# ProgCalc.net
KiCad netlist of a schematic drawn in EAGLE
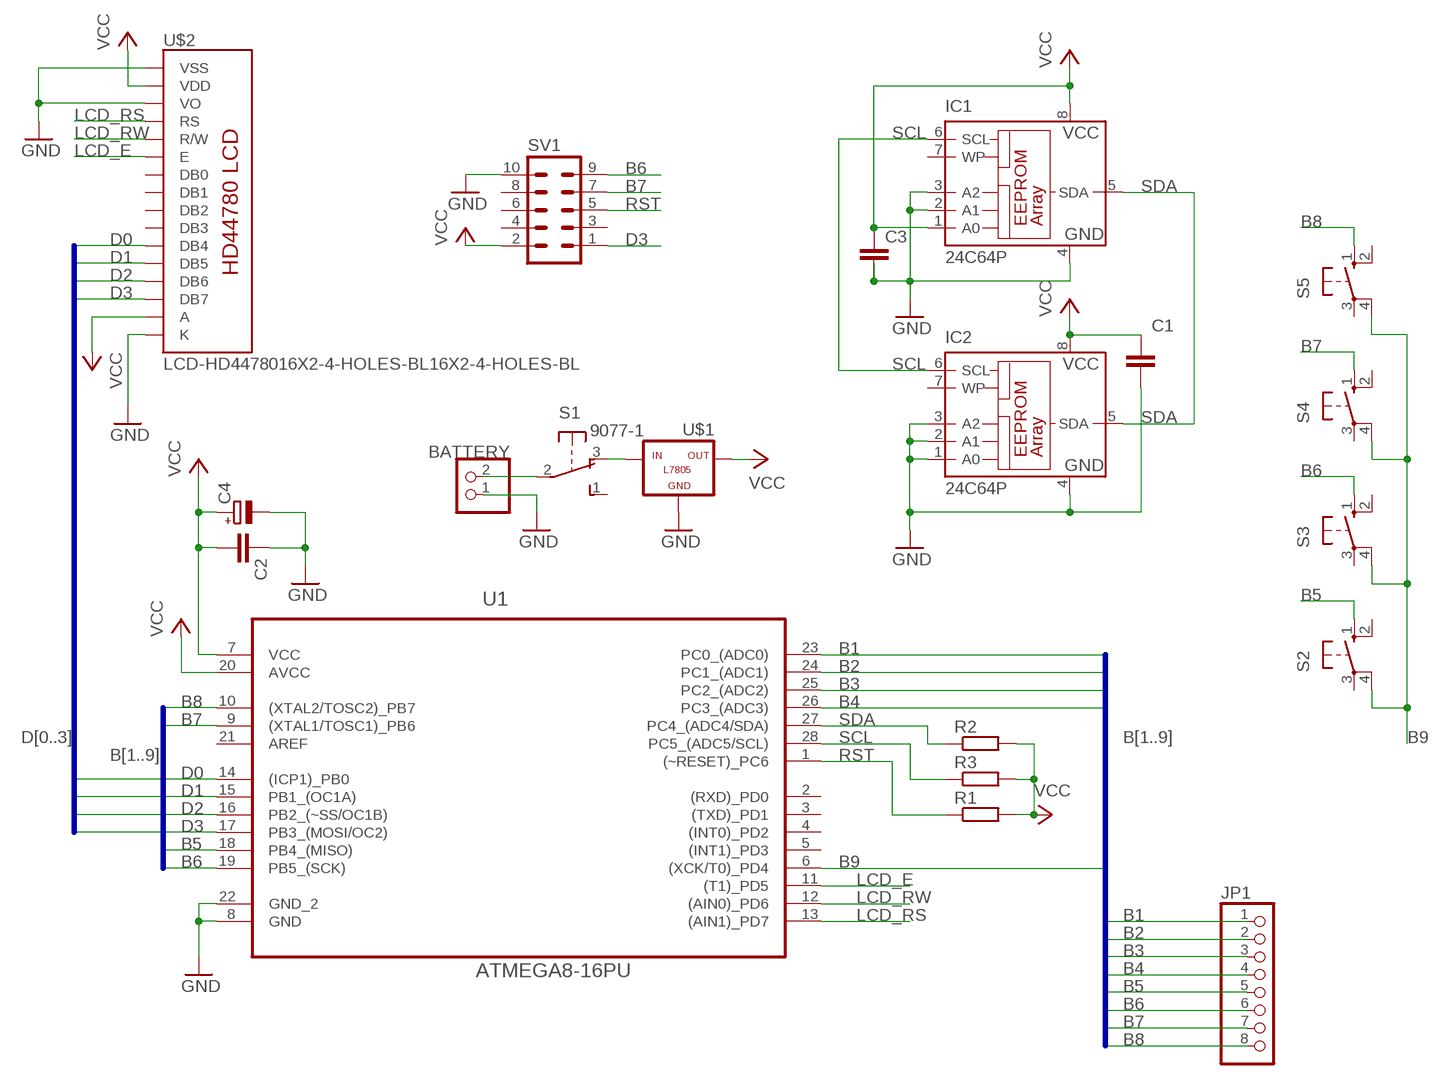
[diagram p0: schematic, sheet 1]

(export (version "E")
  (design (tool "Eeschema 10.0.6"))
  (components
    (comp (ref "BATTERY")
      (value "PINHD-1X2/90")
      (footprint "eagle-import:1X02_90")
      (libsource (lib "eagle-import") (part "PINHD-1X2/90"))
    )
    (comp (ref "C1")
      (value "C-EU025-025X050")
      (footprint "eagle-import:C025-025X050")
      (libsource (lib "eagle-import") (part "C-EU025-025X050"))
    )
    (comp (ref "C2")
      (value "C-EU025-025X050")
      (footprint "eagle-import:C025-025X050")
      (libsource (lib "eagle-import") (part "C-EU025-025X050"))
    )
    (comp (ref "C3")
      (value "C-EU025-025X050")
      (footprint "eagle-import:C025-025X050")
      (libsource (lib "eagle-import") (part "C-EU025-025X050"))
    )
    (comp (ref "C4")
      (value "CPOL-EUE1.8-4")
      (footprint "eagle-import:E1,8-4")
      (libsource (lib "eagle-import") (part "CPOL-EUE1.8-4"))
    )
    (comp (ref "IC1")
      (value "24C64P")
      (footprint "eagle-import:DIL8")
      (fields (field (name "MF") "RAMTRON INTERNATIONAL CORP") (field (name "MPN") "FM24C64-P"))
      (libsource (lib "eagle-import") (part "24PC64"))
    )
    (comp (ref "IC2")
      (value "24C64P")
      (footprint "eagle-import:DIL8")
      (fields (field (name "MF") "RAMTRON INTERNATIONAL CORP") (field (name "MPN") "FM24C64-P"))
      (libsource (lib "eagle-import") (part "24PC64"))
    )
    (comp (ref "JP1")
      (value "PINHD-1X8/90")
      (footprint "eagle-import:1X08_90")
      (libsource (lib "eagle-import") (part "PINHD-1X8/90"))
    )
    (comp (ref "R1")
      (value "R-EU_0204/7")
      (footprint "eagle-import:0204_7")
      (libsource (lib "eagle-import") (part "R-EU_0204/7"))
    )
    (comp (ref "R2")
      (value "R-EU_0204/7")
      (footprint "eagle-import:0204_7")
      (libsource (lib "eagle-import") (part "R-EU_0204/7"))
    )
    (comp (ref "R3")
      (value "R-EU_0204/7")
      (footprint "eagle-import:0204_7")
      (libsource (lib "eagle-import") (part "R-EU_0204/7"))
    )
    (comp (ref "S1")
      (value "9077-1")
      (footprint "eagle-import:9077-1")
      (libsource (lib "eagle-import") (part "9077-1"))
    )
    (comp (ref "S2")
      (value "10-XX")
      (footprint "eagle-import:B3F-10XX")
      (fields (field (name "MPN") "B3F-1000"))
      (libsource (lib "eagle-import") (part "10-XX"))
    )
    (comp (ref "S3")
      (value "10-XX")
      (footprint "eagle-import:B3F-10XX")
      (fields (field (name "MPN") "B3F-1000"))
      (libsource (lib "eagle-import") (part "10-XX"))
    )
    (comp (ref "S4")
      (value "10-XX")
      (footprint "eagle-import:B3F-10XX")
      (fields (field (name "MPN") "B3F-1000"))
      (libsource (lib "eagle-import") (part "10-XX"))
    )
    (comp (ref "S5")
      (value "10-XX")
      (footprint "eagle-import:B3F-10XX")
      (fields (field (name "MPN") "B3F-1000"))
      (libsource (lib "eagle-import") (part "10-XX"))
    )
    (comp (ref "SV1")
      (value "ML10L")
      (footprint "eagle-import:ML10L")
      (libsource (lib "eagle-import") (part "ML10L"))
    )
    (comp (ref "U$1")
      (value "-L7805")
      (footprint "eagle-import:L7805")
      (libsource (lib "eagle-import") (part "-L7805"))
    )
    (comp (ref "U$2")
      (value "LCD-HD4478016X2-4-HOLES-BL16X2-4-HOLES-BL")
      (footprint "eagle-import:LCD-16X2-4HOLES-BL")
      (libsource (lib "eagle-import") (part "LCD-HD4478016X2-4-HOLES-BL16X2-4-HOLES-BL"))
    )
    (comp (ref "U1")
      (value "ATMEGA8-16PU")
      (footprint "eagle-import:DIP254P762X457-28")
      (libsource (lib "eagle-import") (part "ATMEGA8-16PU"))
    )
  )
  (nets
    (net (code "1") (name "/B1") (class "Default")
      (node (ref "JP1") (pin "1") (pinfunction "1_1") (pintype "passive"))
      (node (ref "U1") (pin "23") (pinfunction "PC0_(ADC0)_23") (pintype "bidirectional"))
    )
    (net (code "2") (name "/B2") (class "Default")
      (node (ref "JP1") (pin "2") (pinfunction "2_2") (pintype "passive"))
      (node (ref "U1") (pin "24") (pinfunction "PC1_(ADC1)_24") (pintype "bidirectional"))
    )
    (net (code "3") (name "/B3") (class "Default")
      (node (ref "JP1") (pin "3") (pinfunction "3_3") (pintype "passive"))
      (node (ref "U1") (pin "25") (pinfunction "PC2_(ADC2)_25") (pintype "bidirectional"))
    )
    (net (code "4") (name "/B4") (class "Default")
      (node (ref "JP1") (pin "4") (pinfunction "4_4") (pintype "passive"))
      (node (ref "U1") (pin "26") (pinfunction "PC3_(ADC3)_26") (pintype "bidirectional"))
    )
    (net (code "5") (name "/B5") (class "Default")
      (node (ref "JP1") (pin "5") (pinfunction "5_5") (pintype "passive"))
      (node (ref "S2") (pin "1") (pinfunction "S_1") (pintype "passive"))
      (node (ref "U1") (pin "18") (pinfunction "PB4_(MISO)_18") (pintype "bidirectional"))
    )
    (net (code "6") (name "/B6") (class "Default")
      (node (ref "JP1") (pin "6") (pinfunction "6_6") (pintype "passive"))
      (node (ref "S3") (pin "1") (pinfunction "S_1") (pintype "passive"))
      (node (ref "SV1") (pin "9") (pinfunction "9_9") (pintype "passive"))
      (node (ref "U1") (pin "19") (pinfunction "PB5_(SCK)_19") (pintype "bidirectional"))
    )
    (net (code "7") (name "/B7") (class "Default")
      (node (ref "JP1") (pin "7") (pinfunction "7_7") (pintype "passive"))
      (node (ref "S4") (pin "1") (pinfunction "S_1") (pintype "passive"))
      (node (ref "SV1") (pin "7") (pinfunction "7_7") (pintype "passive"))
      (node (ref "U1") (pin "9") (pinfunction "(XTAL1/TOSC1)_PB6_9") (pintype "input"))
    )
    (net (code "8") (name "/B8") (class "Default")
      (node (ref "JP1") (pin "8") (pinfunction "8_8") (pintype "passive"))
      (node (ref "S5") (pin "1") (pinfunction "S_1") (pintype "passive"))
      (node (ref "U1") (pin "10") (pinfunction "(XTAL2/TOSC2)_PB7_10") (pintype "input"))
    )
    (net (code "9") (name "/B9") (class "Default")
      (node (ref "S2") (pin "4") (pinfunction "P1_4") (pintype "passive"))
      (node (ref "S3") (pin "4") (pinfunction "P1_4") (pintype "passive"))
      (node (ref "S4") (pin "4") (pinfunction "P1_4") (pintype "passive"))
      (node (ref "S5") (pin "4") (pinfunction "P1_4") (pintype "passive"))
      (node (ref "U1") (pin "6") (pinfunction "(XCK/T0)_PD4_6") (pintype "bidirectional"))
    )
    (net (code "11") (name "/D0") (class "Default")
      (node (ref "U$2") (pin "11") (pinfunction "DB4_11") (pintype "bidirectional"))
      (node (ref "U1") (pin "14") (pinfunction "(ICP1)_PB0_14") (pintype "bidirectional"))
    )
    (net (code "12") (name "/D1") (class "Default")
      (node (ref "U$2") (pin "12") (pinfunction "DB5_12") (pintype "bidirectional"))
      (node (ref "U1") (pin "15") (pinfunction "PB1_(OC1A)_15") (pintype "bidirectional"))
    )
    (net (code "13") (name "/D2") (class "Default")
      (node (ref "U$2") (pin "13") (pinfunction "DB6_13") (pintype "bidirectional"))
      (node (ref "U1") (pin "16") (pinfunction "PB2_(~{SS/OC1B})_16") (pintype "bidirectional"))
    )
    (net (code "14") (name "/D3") (class "Default")
      (node (ref "SV1") (pin "1") (pinfunction "1_1") (pintype "passive"))
      (node (ref "U$2") (pin "14") (pinfunction "DB7_14") (pintype "bidirectional"))
      (node (ref "U1") (pin "17") (pinfunction "PB3_(MOSI/OC2)_17") (pintype "bidirectional"))
    )
    (net (code "16") (name "/LCD_E") (class "Default")
      (node (ref "U$2") (pin "6") (pinfunction "E_6") (pintype "input"))
      (node (ref "U1") (pin "11") (pinfunction "(T1)_PD5_11") (pintype "bidirectional"))
    )
    (net (code "17") (name "/LCD_RS") (class "Default")
      (node (ref "U$2") (pin "4") (pinfunction "RS_4") (pintype "input"))
      (node (ref "U1") (pin "13") (pinfunction "(AIN1)_PD7_13") (pintype "bidirectional"))
    )
    (net (code "18") (name "/LCD_RW") (class "Default")
      (node (ref "U$2") (pin "5") (pinfunction "R/W_5") (pintype "input"))
      (node (ref "U1") (pin "12") (pinfunction "(AIN0)_PD6_12") (pintype "bidirectional"))
    )
    (net (code "19") (name "/RST") (class "Default")
      (node (ref "R1") (pin "1") (pinfunction "1_1") (pintype "passive"))
      (node (ref "SV1") (pin "5") (pinfunction "5_5") (pintype "passive"))
      (node (ref "U1") (pin "1") (pinfunction "(~{RESET})_PC6_1") (pintype "bidirectional"))
    )
    (net (code "20") (name "/SCL") (class "Default")
      (node (ref "IC1") (pin "6") (pinfunction "SCL_6") (pintype "input"))
      (node (ref "IC2") (pin "6") (pinfunction "SCL_6") (pintype "input"))
      (node (ref "R3") (pin "1") (pinfunction "1_1") (pintype "passive"))
      (node (ref "U1") (pin "28") (pinfunction "PC5_(ADC5/SCL)_28") (pintype "bidirectional"))
    )
    (net (code "21") (name "/SDA") (class "Default")
      (node (ref "IC1") (pin "5") (pinfunction "SDA_5") (pintype "bidirectional"))
      (node (ref "IC2") (pin "5") (pinfunction "SDA_5") (pintype "bidirectional"))
      (node (ref "R2") (pin "1") (pinfunction "1_1") (pintype "passive"))
      (node (ref "U1") (pin "27") (pinfunction "PC4_(ADC4/SDA)_27") (pintype "bidirectional"))
    )
    (net (code "22") (name "GND") (class "Default")
      (node (ref "BATTERY") (pin "1") (pinfunction "1_1") (pintype "passive"))
      (node (ref "C1") (pin "2") (pinfunction "2_2") (pintype "passive"))
      (node (ref "C2") (pin "1") (pinfunction "1_1") (pintype "passive"))
      (node (ref "C3") (pin "2") (pinfunction "2_2") (pintype "passive"))
      (node (ref "C4") (pin "-") (pinfunction "-_-") (pintype "passive"))
      (node (ref "IC1") (pin "2") (pinfunction "A1_2") (pintype "input"))
      (node (ref "IC1") (pin "3") (pinfunction "A2_3") (pintype "input"))
      (node (ref "IC1") (pin "4") (pinfunction "GND_4") (pintype "power_in"))
      (node (ref "IC2") (pin "1") (pinfunction "A0_1") (pintype "input"))
      (node (ref "IC2") (pin "2") (pinfunction "A1_2") (pintype "input"))
      (node (ref "IC2") (pin "3") (pinfunction "A2_3") (pintype "input"))
      (node (ref "IC2") (pin "4") (pinfunction "GND_4") (pintype "power_in"))
      (node (ref "SV1") (pin "10") (pinfunction "10_10") (pintype "passive"))
      (node (ref "U$1") (pin "GND") (pinfunction "GND_GND") (pintype "input"))
      (node (ref "U$2") (pin "1") (pinfunction "VSS_1") (pintype "power_in"))
      (node (ref "U$2") (pin "16") (pinfunction "K_16") (pintype "power_in"))
      (node (ref "U$2") (pin "3") (pinfunction "VO_3") (pintype "bidirectional"))
      (node (ref "U1") (pin "22") (pinfunction "GND_2_22") (pintype "passive"))
      (node (ref "U1") (pin "8") (pinfunction "GND_8") (pintype "passive"))
    )
    (net (code "23") (name "Net-(S1-O)") (class "Default")
      (node (ref "S1") (pin "3") (pinfunction "O_3") (pintype "passive"))
      (node (ref "U$1") (pin "IN") (pinfunction "IN_IN") (pintype "input"))
    )
    (net (code "24") (name "Net-(S1-P)") (class "Default")
      (node (ref "BATTERY") (pin "2") (pinfunction "2_2") (pintype "passive"))
      (node (ref "S1") (pin "2") (pinfunction "P_2") (pintype "passive"))
    )
    (net (code "25") (name "VCC") (class "Default")
      (node (ref "C1") (pin "1") (pinfunction "1_1") (pintype "passive"))
      (node (ref "C2") (pin "2") (pinfunction "2_2") (pintype "passive"))
      (node (ref "C3") (pin "1") (pinfunction "1_1") (pintype "passive"))
      (node (ref "C4") (pin "+") (pinfunction "+_+") (pintype "passive"))
      (node (ref "IC1") (pin "1") (pinfunction "A0_1") (pintype "input"))
      (node (ref "IC1") (pin "8") (pinfunction "VCC_8") (pintype "power_in"))
      (node (ref "IC2") (pin "8") (pinfunction "VCC_8") (pintype "power_in"))
      (node (ref "R1") (pin "2") (pinfunction "2_2") (pintype "passive"))
      (node (ref "R2") (pin "2") (pinfunction "2_2") (pintype "passive"))
      (node (ref "R3") (pin "2") (pinfunction "2_2") (pintype "passive"))
      (node (ref "SV1") (pin "2") (pinfunction "2_2") (pintype "passive"))
      (node (ref "U$1") (pin "OUT") (pinfunction "OUT_OUT") (pintype "passive"))
      (node (ref "U$2") (pin "15") (pinfunction "A_15") (pintype "power_in"))
      (node (ref "U$2") (pin "2") (pinfunction "VDD_2") (pintype "power_in"))
      (node (ref "U1") (pin "20") (pinfunction "AVCC_20") (pintype "power_in"))
      (node (ref "U1") (pin "7") (pinfunction "VCC_7") (pintype "power_in"))
    )
    (net (code "26") (name "unconnected-(IC1-WP-Pad7)") (class "Default")
      (node (ref "IC1") (pin "7") (pinfunction "WP_7") (pintype "input"))
    )
    (net (code "27") (name "unconnected-(IC2-WP-Pad7)") (class "Default")
      (node (ref "IC2") (pin "7") (pinfunction "WP_7") (pintype "input"))
    )
    (net (code "28") (name "unconnected-(S1-S-Pad1)") (class "Default")
      (node (ref "S1") (pin "1") (pinfunction "S_1") (pintype "passive"))
    )
    (net (code "29") (name "unconnected-(S2-P-Pad3)") (class "Default")
      (node (ref "S2") (pin "3") (pinfunction "P_3") (pintype "passive"))
    )
    (net (code "30") (name "unconnected-(S2-S1-Pad2)") (class "Default")
      (node (ref "S2") (pin "2") (pinfunction "S1_2") (pintype "passive"))
    )
    (net (code "31") (name "unconnected-(S3-P-Pad3)") (class "Default")
      (node (ref "S3") (pin "3") (pinfunction "P_3") (pintype "passive"))
    )
    (net (code "32") (name "unconnected-(S3-S1-Pad2)") (class "Default")
      (node (ref "S3") (pin "2") (pinfunction "S1_2") (pintype "passive"))
    )
    (net (code "33") (name "unconnected-(S4-P-Pad3)") (class "Default")
      (node (ref "S4") (pin "3") (pinfunction "P_3") (pintype "passive"))
    )
    (net (code "34") (name "unconnected-(S4-S1-Pad2)") (class "Default")
      (node (ref "S4") (pin "2") (pinfunction "S1_2") (pintype "passive"))
    )
    (net (code "35") (name "unconnected-(S5-P-Pad3)") (class "Default")
      (node (ref "S5") (pin "3") (pinfunction "P_3") (pintype "passive"))
    )
    (net (code "36") (name "unconnected-(S5-S1-Pad2)") (class "Default")
      (node (ref "S5") (pin "2") (pinfunction "S1_2") (pintype "passive"))
    )
    (net (code "37") (name "unconnected-(SV1-Pad3)") (class "Default")
      (node (ref "SV1") (pin "3") (pinfunction "3_3") (pintype "passive"))
    )
    (net (code "38") (name "unconnected-(SV1-Pad4)") (class "Default")
      (node (ref "SV1") (pin "4") (pinfunction "4_4") (pintype "passive"))
    )
    (net (code "39") (name "unconnected-(SV1-Pad6)") (class "Default")
      (node (ref "SV1") (pin "6") (pinfunction "6_6") (pintype "passive"))
    )
    (net (code "40") (name "unconnected-(SV1-Pad8)") (class "Default")
      (node (ref "SV1") (pin "8") (pinfunction "8_8") (pintype "passive"))
    )
    (net (code "41") (name "unconnected-(U$2-DB0-Pad7)") (class "Default")
      (node (ref "U$2") (pin "7") (pinfunction "DB0_7") (pintype "bidirectional"))
    )
    (net (code "42") (name "unconnected-(U$2-DB1-Pad8)") (class "Default")
      (node (ref "U$2") (pin "8") (pinfunction "DB1_8") (pintype "bidirectional"))
    )
    (net (code "43") (name "unconnected-(U$2-DB2-Pad9)") (class "Default")
      (node (ref "U$2") (pin "9") (pinfunction "DB2_9") (pintype "bidirectional"))
    )
    (net (code "44") (name "unconnected-(U$2-DB3-Pad10)") (class "Default")
      (node (ref "U$2") (pin "10") (pinfunction "DB3_10") (pintype "bidirectional"))
    )
    (net (code "45") (name "unconnected-(U1-(INT0)_PD2-Pad4)") (class "Default")
      (node (ref "U1") (pin "4") (pinfunction "(INT0)_PD2_4") (pintype "bidirectional"))
    )
    (net (code "46") (name "unconnected-(U1-(INT1)_PD3-Pad5)") (class "Default")
      (node (ref "U1") (pin "5") (pinfunction "(INT1)_PD3_5") (pintype "bidirectional"))
    )
    (net (code "47") (name "unconnected-(U1-(RXD)_PD0-Pad2)") (class "Default")
      (node (ref "U1") (pin "2") (pinfunction "(RXD)_PD0_2") (pintype "bidirectional"))
    )
    (net (code "48") (name "unconnected-(U1-(TXD)_PD1-Pad3)") (class "Default")
      (node (ref "U1") (pin "3") (pinfunction "(TXD)_PD1_3") (pintype "bidirectional"))
    )
    (net (code "49") (name "unconnected-(U1-AREF-Pad21)") (class "Default")
      (node (ref "U1") (pin "21") (pinfunction "AREF_21") (pintype "input"))
    )
  )
)
